# enviroAccelerometer.net
KiCad netlist of a schematic drawn in Altium Designer
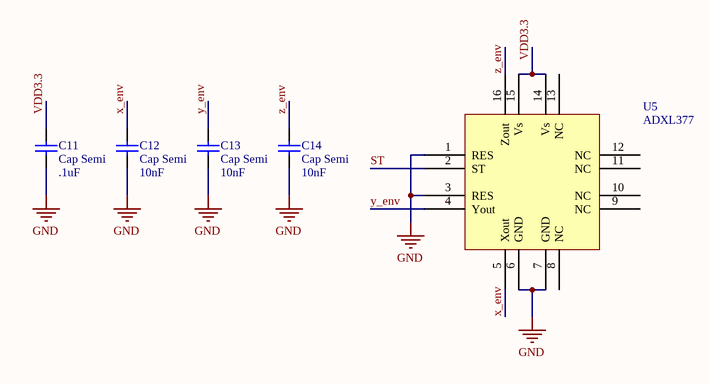
[diagram p0: enviroAccelerometer.SchDoc]

(export (version "E")
  (design (tool "Eeschema 10.0.6"))
  (components
    (comp (ref "C11")
      (value "Cap Semi")
      (footprint "C1206")
      (description "Capacitor (Semiconductor SIM Model)")
      (fields (field (name "ALTIUM_VALUE") ".1uF") (field (name "PUBLISHER") "Altium Limited"))
      (libsource (lib "Miscellaneous Devices") (part "Cap Semi"))
    )
    (comp (ref "C12")
      (value "Cap Semi")
      (footprint "C1206")
      (description "Capacitor (Semiconductor SIM Model)")
      (fields (field (name "ALTIUM_VALUE") "10nF") (field (name "PUBLISHER") "Altium Limited"))
      (libsource (lib "Miscellaneous Devices") (part "Cap Semi"))
    )
    (comp (ref "C13")
      (value "Cap Semi")
      (footprint "C1206")
      (description "Capacitor (Semiconductor SIM Model)")
      (fields (field (name "ALTIUM_VALUE") "10nF") (field (name "PUBLISHER") "Altium Limited"))
      (libsource (lib "Miscellaneous Devices") (part "Cap Semi"))
    )
    (comp (ref "C14")
      (value "Cap Semi")
      (footprint "C1206")
      (description "Capacitor (Semiconductor SIM Model)")
      (fields (field (name "ALTIUM_VALUE") "10nF") (field (name "PUBLISHER") "Altium Limited"))
      (libsource (lib "Miscellaneous Devices") (part "Cap Semi"))
    )
    (comp (ref "U5")
      (value "ADXL377")
      (footprint "ADXL377")
      (libsource (lib "environmentalAccelerometer") (part "ADXL377"))
    )
  )
  (nets
    (net (code "1") (name "/ST") (class "Default")
      (node (ref "U5") (pin "2") (pinfunction "ST_2") (pintype "passive"))
    )
    (net (code "2") (name "/VDD3.3") (class "Default")
      (node (ref "C11") (pin "1") (pinfunction "1_1") (pintype "passive"))
      (node (ref "U5") (pin "14") (pinfunction "Vs_14") (pintype "passive"))
      (node (ref "U5") (pin "15") (pinfunction "Vs_15") (pintype "passive"))
    )
    (net (code "3") (name "/x_env") (class "Default")
      (node (ref "C12") (pin "2") (pinfunction "2_2") (pintype "passive"))
      (node (ref "U5") (pin "5") (pinfunction "Xout_5") (pintype "passive"))
    )
    (net (code "4") (name "/y_env") (class "Default")
      (node (ref "C13") (pin "2") (pinfunction "2_2") (pintype "passive"))
      (node (ref "U5") (pin "4") (pinfunction "Yout_4") (pintype "passive"))
    )
    (net (code "5") (name "/z_env") (class "Default")
      (node (ref "C14") (pin "2") (pinfunction "2_2") (pintype "passive"))
      (node (ref "U5") (pin "16") (pinfunction "Zout_16") (pintype "passive"))
    )
    (net (code "6") (name "GND") (class "Default")
      (node (ref "C11") (pin "2") (pinfunction "2_2") (pintype "passive"))
      (node (ref "C12") (pin "1") (pinfunction "1_1") (pintype "passive"))
      (node (ref "C13") (pin "1") (pinfunction "1_1") (pintype "passive"))
      (node (ref "C14") (pin "1") (pinfunction "1_1") (pintype "passive"))
      (node (ref "U5") (pin "1") (pinfunction "RES_1") (pintype "passive"))
      (node (ref "U5") (pin "3") (pinfunction "RES_3") (pintype "passive"))
      (node (ref "U5") (pin "6") (pinfunction "GND_6") (pintype "passive"))
      (node (ref "U5") (pin "7") (pinfunction "GND_7") (pintype "passive"))
    )
    (net (code "7") (name "unconnected-(U5-NC-Pad8)") (class "Default")
      (node (ref "U5") (pin "8") (pinfunction "NC_8") (pintype "passive"))
    )
    (net (code "8") (name "unconnected-(U5-NC-Pad9)") (class "Default")
      (node (ref "U5") (pin "9") (pinfunction "NC_9") (pintype "passive"))
    )
    (net (code "9") (name "unconnected-(U5-NC-Pad10)") (class "Default")
      (node (ref "U5") (pin "10") (pinfunction "NC_10") (pintype "passive"))
    )
    (net (code "10") (name "unconnected-(U5-NC-Pad11)") (class "Default")
      (node (ref "U5") (pin "11") (pinfunction "NC_11") (pintype "passive"))
    )
    (net (code "11") (name "unconnected-(U5-NC-Pad12)") (class "Default")
      (node (ref "U5") (pin "12") (pinfunction "NC_12") (pintype "passive"))
    )
    (net (code "12") (name "unconnected-(U5-NC-Pad13)") (class "Default")
      (node (ref "U5") (pin "13") (pinfunction "NC_13") (pintype "passive"))
    )
  )
)
